# Matrix.net
KiCad netlist of a schematic drawn in Altium Designer
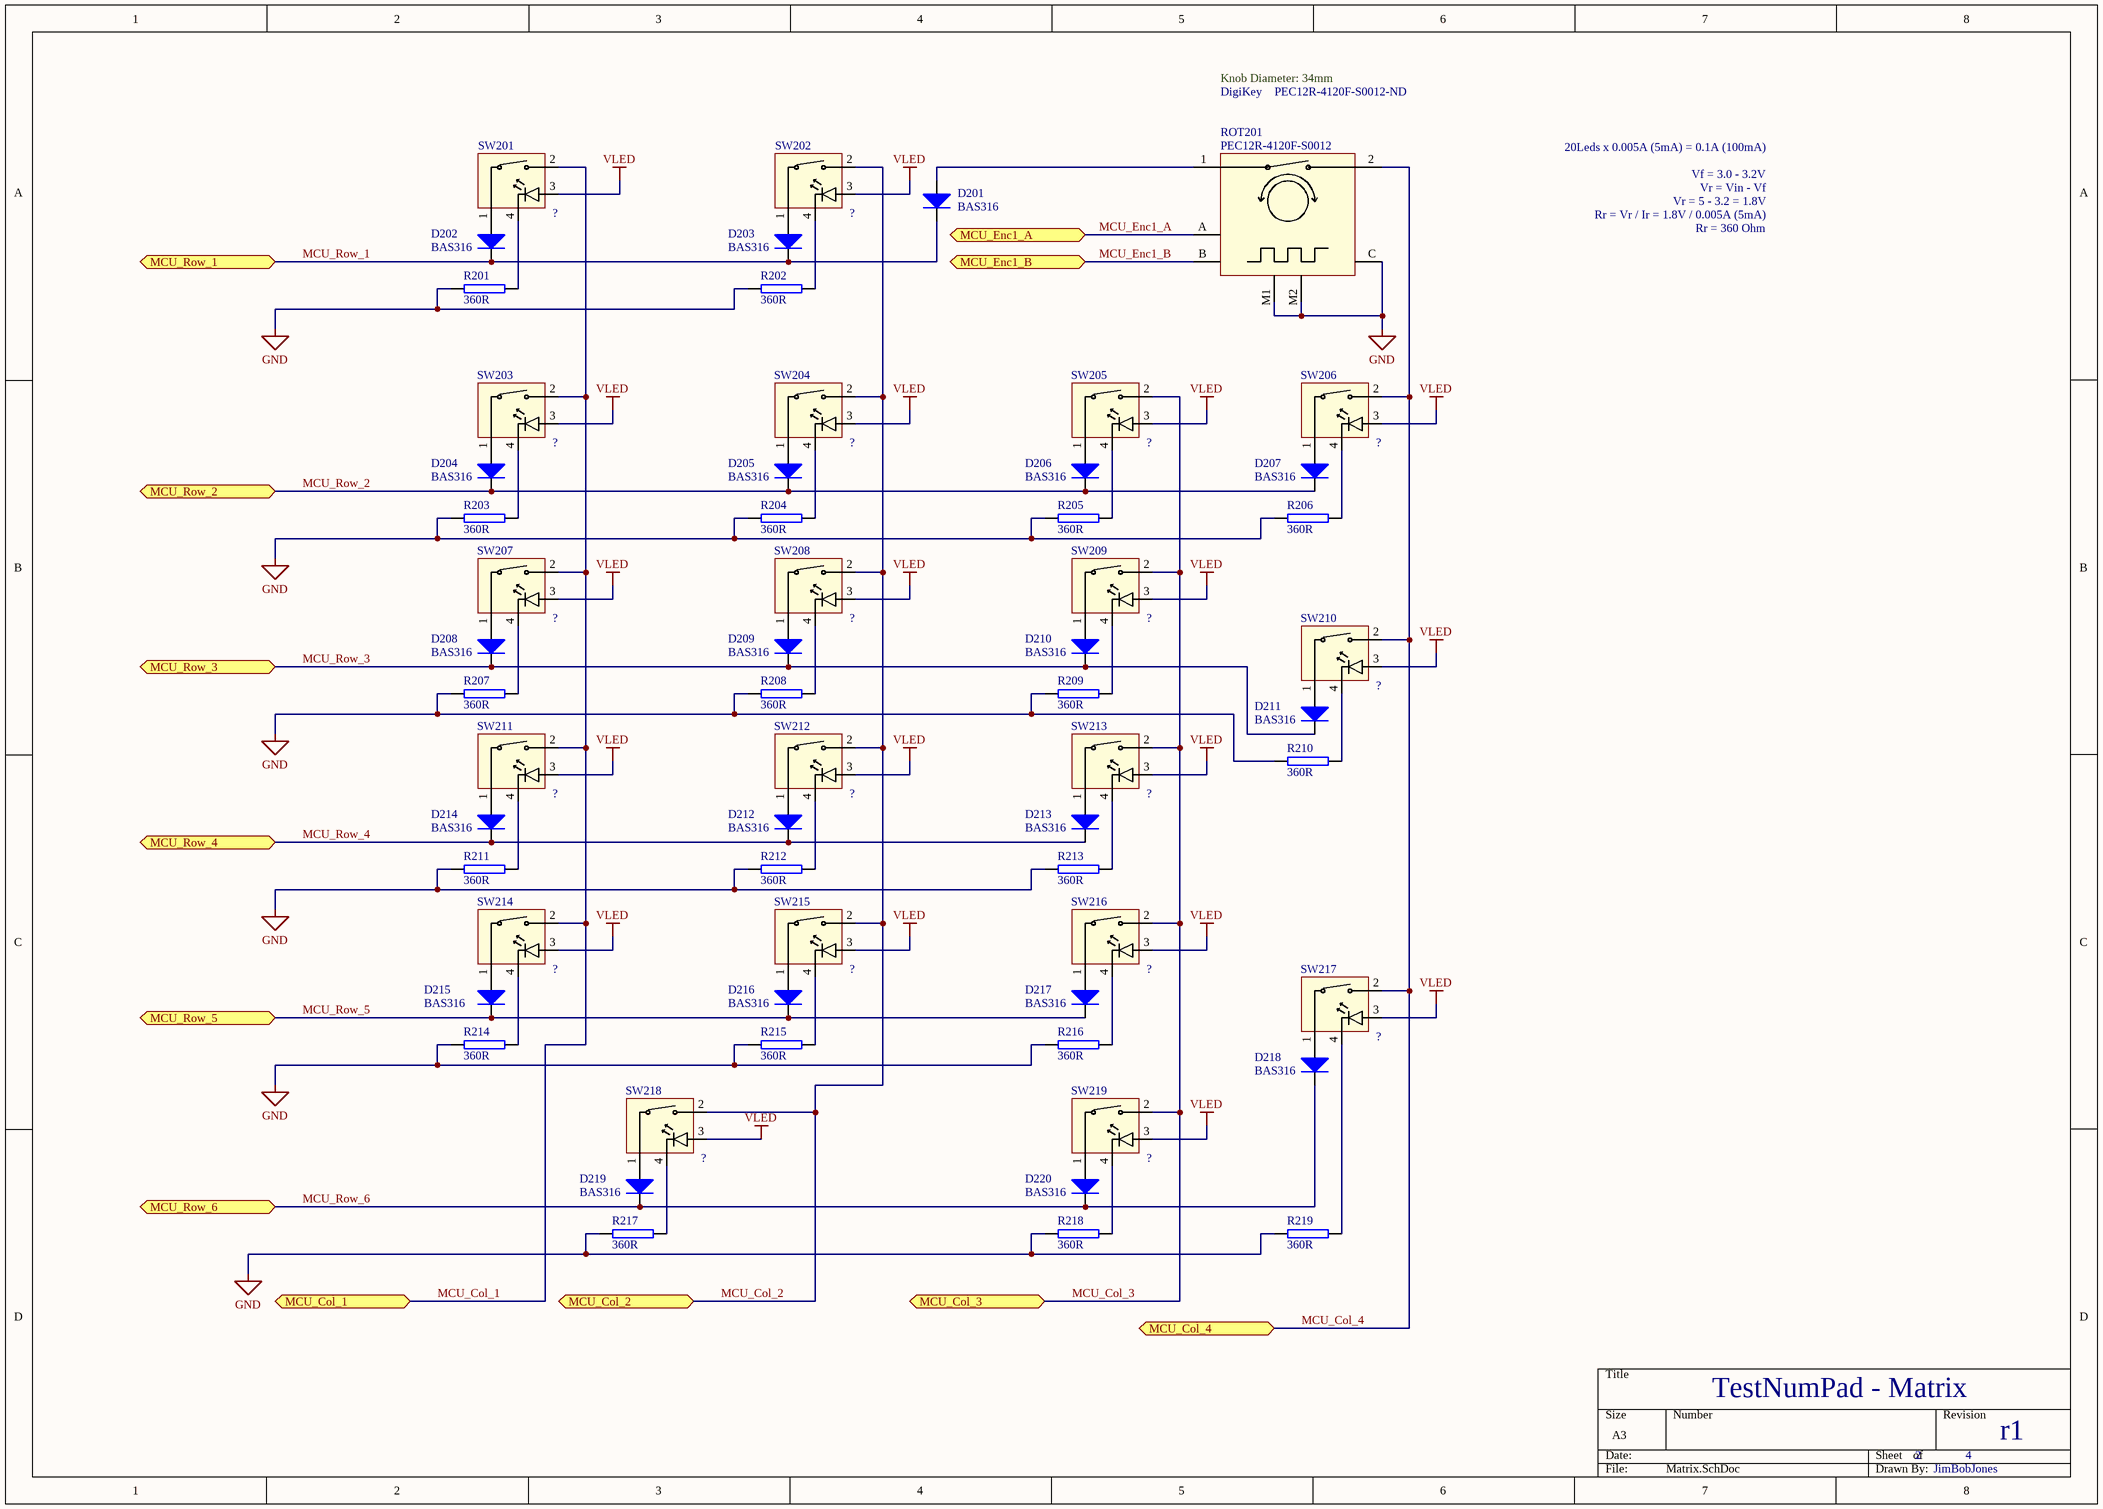
[diagram p0: Matrix.SchDoc]

(export (version "E")
  (design (tool "Eeschema 10.0.6"))
  (components
    (comp (ref "D201")
      (value "BAS316")
      (footprint "SOD110/SOD323")
      (description "Signal diode, 100V, 250mA, 400mW")
      (libsource (lib "JM_Keyboard") (part "Diode-BAS316"))
    )
    (comp (ref "D202")
      (value "BAS316")
      (footprint "SOD110/SOD323")
      (description "Signal diode, 100V, 250mA, 400mW")
      (libsource (lib "JM_Keyboard") (part "Diode-BAS316"))
    )
    (comp (ref "D203")
      (value "BAS316")
      (footprint "SOD110/SOD323")
      (description "Signal diode, 100V, 250mA, 400mW")
      (libsource (lib "JM_Keyboard") (part "Diode-BAS316"))
    )
    (comp (ref "D204")
      (value "BAS316")
      (footprint "SOD110/SOD323")
      (description "Signal diode, 100V, 250mA, 400mW")
      (libsource (lib "JM_Keyboard") (part "Diode-BAS316"))
    )
    (comp (ref "D205")
      (value "BAS316")
      (footprint "SOD110/SOD323")
      (description "Signal diode, 100V, 250mA, 400mW")
      (libsource (lib "JM_Keyboard") (part "Diode-BAS316"))
    )
    (comp (ref "D206")
      (value "BAS316")
      (footprint "SOD110/SOD323")
      (description "Signal diode, 100V, 250mA, 400mW")
      (libsource (lib "JM_Keyboard") (part "Diode-BAS316"))
    )
    (comp (ref "D207")
      (value "BAS316")
      (footprint "SOD110/SOD323")
      (description "Signal diode, 100V, 250mA, 400mW")
      (libsource (lib "JM_Keyboard") (part "Diode-BAS316"))
    )
    (comp (ref "D208")
      (value "BAS316")
      (footprint "SOD110/SOD323")
      (description "Signal diode, 100V, 250mA, 400mW")
      (libsource (lib "JM_Keyboard") (part "Diode-BAS316"))
    )
    (comp (ref "D209")
      (value "BAS316")
      (footprint "SOD110/SOD323")
      (description "Signal diode, 100V, 250mA, 400mW")
      (libsource (lib "JM_Keyboard") (part "Diode-BAS316"))
    )
    (comp (ref "D210")
      (value "BAS316")
      (footprint "SOD110/SOD323")
      (description "Signal diode, 100V, 250mA, 400mW")
      (libsource (lib "JM_Keyboard") (part "Diode-BAS316"))
    )
    (comp (ref "D211")
      (value "BAS316")
      (footprint "SOD110/SOD323")
      (description "Signal diode, 100V, 250mA, 400mW")
      (libsource (lib "JM_Keyboard") (part "Diode-BAS316"))
    )
    (comp (ref "D212")
      (value "BAS316")
      (footprint "SOD110/SOD323")
      (description "Signal diode, 100V, 250mA, 400mW")
      (libsource (lib "JM_Keyboard") (part "Diode-BAS316"))
    )
    (comp (ref "D213")
      (value "BAS316")
      (footprint "SOD110/SOD323")
      (description "Signal diode, 100V, 250mA, 400mW")
      (libsource (lib "JM_Keyboard") (part "Diode-BAS316"))
    )
    (comp (ref "D214")
      (value "BAS316")
      (footprint "SOD110/SOD323")
      (description "Signal diode, 100V, 250mA, 400mW")
      (libsource (lib "JM_Keyboard") (part "Diode-BAS316"))
    )
    (comp (ref "D215")
      (value "BAS316")
      (footprint "SOD110/SOD323")
      (description "Signal diode, 100V, 250mA, 400mW")
      (libsource (lib "JM_Keyboard") (part "Diode-BAS316"))
    )
    (comp (ref "D216")
      (value "BAS316")
      (footprint "SOD110/SOD323")
      (description "Signal diode, 100V, 250mA, 400mW")
      (libsource (lib "JM_Keyboard") (part "Diode-BAS316"))
    )
    (comp (ref "D217")
      (value "BAS316")
      (footprint "SOD110/SOD323")
      (description "Signal diode, 100V, 250mA, 400mW")
      (libsource (lib "JM_Keyboard") (part "Diode-BAS316"))
    )
    (comp (ref "D218")
      (value "BAS316")
      (footprint "SOD110/SOD323")
      (description "Signal diode, 100V, 250mA, 400mW")
      (libsource (lib "JM_Keyboard") (part "Diode-BAS316"))
    )
    (comp (ref "D219")
      (value "BAS316")
      (footprint "SOD110/SOD323")
      (description "Signal diode, 100V, 250mA, 400mW")
      (libsource (lib "JM_Keyboard") (part "Diode-BAS316"))
    )
    (comp (ref "D220")
      (value "BAS316")
      (footprint "SOD110/SOD323")
      (description "Signal diode, 100V, 250mA, 400mW")
      (libsource (lib "JM_Keyboard") (part "Diode-BAS316"))
    )
    (comp (ref "R201")
      (value "360R")
      (footprint "2012R-360")
      (description "RESISTOR 2012 1/4 WATT THIN FILM")
      (libsource (lib "JM_Keyboard") (part "2012R-360"))
    )
    (comp (ref "R202")
      (value "360R")
      (footprint "2012R-360")
      (description "RESISTOR 2012 1/4 WATT THIN FILM")
      (libsource (lib "JM_Keyboard") (part "2012R-360"))
    )
    (comp (ref "R203")
      (value "360R")
      (footprint "2012R-360")
      (description "RESISTOR 2012 1/4 WATT THIN FILM")
      (libsource (lib "JM_Keyboard") (part "2012R-360"))
    )
    (comp (ref "R204")
      (value "360R")
      (footprint "2012R-360")
      (description "RESISTOR 2012 1/4 WATT THIN FILM")
      (libsource (lib "JM_Keyboard") (part "2012R-360"))
    )
    (comp (ref "R205")
      (value "360R")
      (footprint "2012R-360")
      (description "RESISTOR 2012 1/4 WATT THIN FILM")
      (libsource (lib "JM_Keyboard") (part "2012R-360"))
    )
    (comp (ref "R206")
      (value "360R")
      (footprint "2012R-360")
      (description "RESISTOR 2012 1/4 WATT THIN FILM")
      (libsource (lib "JM_Keyboard") (part "2012R-360"))
    )
    (comp (ref "R207")
      (value "360R")
      (footprint "2012R-360")
      (description "RESISTOR 2012 1/4 WATT THIN FILM")
      (libsource (lib "JM_Keyboard") (part "2012R-360"))
    )
    (comp (ref "R208")
      (value "360R")
      (footprint "2012R-360")
      (description "RESISTOR 2012 1/4 WATT THIN FILM")
      (libsource (lib "JM_Keyboard") (part "2012R-360"))
    )
    (comp (ref "R209")
      (value "360R")
      (footprint "2012R-360")
      (description "RESISTOR 2012 1/4 WATT THIN FILM")
      (libsource (lib "JM_Keyboard") (part "2012R-360"))
    )
    (comp (ref "R210")
      (value "360R")
      (footprint "2012R-360")
      (description "RESISTOR 2012 1/4 WATT THIN FILM")
      (libsource (lib "JM_Keyboard") (part "2012R-360"))
    )
    (comp (ref "R211")
      (value "360R")
      (footprint "2012R-360")
      (description "RESISTOR 2012 1/4 WATT THIN FILM")
      (libsource (lib "JM_Keyboard") (part "2012R-360"))
    )
    (comp (ref "R212")
      (value "360R")
      (footprint "2012R-360")
      (description "RESISTOR 2012 1/4 WATT THIN FILM")
      (libsource (lib "JM_Keyboard") (part "2012R-360"))
    )
    (comp (ref "R213")
      (value "360R")
      (footprint "2012R-360")
      (description "RESISTOR 2012 1/4 WATT THIN FILM")
      (libsource (lib "JM_Keyboard") (part "2012R-360"))
    )
    (comp (ref "R214")
      (value "360R")
      (footprint "2012R-360")
      (description "RESISTOR 2012 1/4 WATT THIN FILM")
      (libsource (lib "JM_Keyboard") (part "2012R-360"))
    )
    (comp (ref "R215")
      (value "360R")
      (footprint "2012R-360")
      (description "RESISTOR 2012 1/4 WATT THIN FILM")
      (libsource (lib "JM_Keyboard") (part "2012R-360"))
    )
    (comp (ref "R216")
      (value "360R")
      (footprint "2012R-360")
      (description "RESISTOR 2012 1/4 WATT THIN FILM")
      (libsource (lib "JM_Keyboard") (part "2012R-360"))
    )
    (comp (ref "R217")
      (value "360R")
      (footprint "2012R-360")
      (description "RESISTOR 2012 1/4 WATT THIN FILM")
      (libsource (lib "JM_Keyboard") (part "2012R-360"))
    )
    (comp (ref "R218")
      (value "360R")
      (footprint "2012R-360")
      (description "RESISTOR 2012 1/4 WATT THIN FILM")
      (libsource (lib "JM_Keyboard") (part "2012R-360"))
    )
    (comp (ref "R219")
      (value "360R")
      (footprint "2012R-360")
      (description "RESISTOR 2012 1/4 WATT THIN FILM")
      (libsource (lib "JM_Keyboard") (part "2012R-360"))
    )
    (comp (ref "ROT201")
      (value "PEC12R-4120F-S0012")
      (footprint "PEC12R-4xxxF-Sxxxx-NoMod")
      (description "Burns 6mm D-shaft 2-Ch Rotary Encoder with switch, 12ppr, Vertical")
      (fields (field (name "SUPPLIER PART NUMBER 1") "PEC12R-4120F-S0012-ND"))
      (libsource (lib "JM_Keyboard") (part "PEC12R-Vert-Sw"))
    )
    (comp (ref "SW201")
      (value "MX_Apls")
      (footprint "MX-1U")
      (description "1U - MX_Alps Hybrid Footprint")
      (fields (field (name "KEY") "?"))
      (libsource (lib "JM_Keyboard") (part "MX-LED-1U"))
    )
    (comp (ref "SW202")
      (value "MX_Apls")
      (footprint "MX-1U")
      (description "1U - MX_Alps Hybrid Footprint")
      (fields (field (name "KEY") "?"))
      (libsource (lib "JM_Keyboard") (part "MX-LED-1U"))
    )
    (comp (ref "SW203")
      (value "MX_Apls")
      (footprint "MX-1U")
      (description "1U - MX_Alps Hybrid Footprint")
      (fields (field (name "KEY") "?"))
      (libsource (lib "JM_Keyboard") (part "MX-LED-1U"))
    )
    (comp (ref "SW204")
      (value "MX_Apls")
      (footprint "MX-1U")
      (description "1U - MX_Alps Hybrid Footprint")
      (fields (field (name "KEY") "?"))
      (libsource (lib "JM_Keyboard") (part "MX-LED-1U"))
    )
    (comp (ref "SW205")
      (value "MX_Apls")
      (footprint "MX-1U")
      (description "1U - MX_Alps Hybrid Footprint")
      (fields (field (name "KEY") "?"))
      (libsource (lib "JM_Keyboard") (part "MX-LED-1U"))
    )
    (comp (ref "SW206")
      (value "MX_Apls")
      (footprint "MX-1U")
      (description "1U - MX_Alps Hybrid Footprint")
      (fields (field (name "KEY") "?"))
      (libsource (lib "JM_Keyboard") (part "MX-LED-1U"))
    )
    (comp (ref "SW207")
      (value "MX_Apls")
      (footprint "MX-1U")
      (description "1U - MX_Alps Hybrid Footprint")
      (fields (field (name "KEY") "?"))
      (libsource (lib "JM_Keyboard") (part "MX-LED-1U"))
    )
    (comp (ref "SW208")
      (value "MX_Apls")
      (footprint "MX-1U")
      (description "1U - MX_Alps Hybrid Footprint")
      (fields (field (name "KEY") "?"))
      (libsource (lib "JM_Keyboard") (part "MX-LED-1U"))
    )
    (comp (ref "SW209")
      (value "MX_Apls")
      (footprint "MX-1U")
      (description "1U - MX_Alps Hybrid Footprint")
      (fields (field (name "KEY") "?"))
      (libsource (lib "JM_Keyboard") (part "MX-LED-1U"))
    )
    (comp (ref "SW210")
      (value "MX_Apls")
      (footprint "MX-2U")
      (description "1U - MX_Alps Hybrid Footprint")
      (fields (field (name "KEY") "?"))
      (libsource (lib "JM_Keyboard") (part "MX-LED-1U"))
    )
    (comp (ref "SW211")
      (value "MX_Apls")
      (footprint "MX-1U")
      (description "1U - MX_Alps Hybrid Footprint")
      (fields (field (name "KEY") "?"))
      (libsource (lib "JM_Keyboard") (part "MX-LED-1U"))
    )
    (comp (ref "SW212")
      (value "MX_Apls")
      (footprint "MX-1U")
      (description "1U - MX_Alps Hybrid Footprint")
      (fields (field (name "KEY") "?"))
      (libsource (lib "JM_Keyboard") (part "MX-LED-1U"))
    )
    (comp (ref "SW213")
      (value "MX_Apls")
      (footprint "MX-1U")
      (description "1U - MX_Alps Hybrid Footprint")
      (fields (field (name "KEY") "?"))
      (libsource (lib "JM_Keyboard") (part "MX-LED-1U"))
    )
    (comp (ref "SW214")
      (value "MX_Apls")
      (footprint "MX-1U")
      (description "1U - MX_Alps Hybrid Footprint")
      (fields (field (name "KEY") "?"))
      (libsource (lib "JM_Keyboard") (part "MX-LED-1U"))
    )
    (comp (ref "SW215")
      (value "MX_Apls")
      (footprint "MX-1U")
      (description "1U - MX_Alps Hybrid Footprint")
      (fields (field (name "KEY") "?"))
      (libsource (lib "JM_Keyboard") (part "MX-LED-1U"))
    )
    (comp (ref "SW216")
      (value "MX_Apls")
      (footprint "MX-1U")
      (description "1U - MX_Alps Hybrid Footprint")
      (fields (field (name "KEY") "?"))
      (libsource (lib "JM_Keyboard") (part "MX-LED-1U"))
    )
    (comp (ref "SW217")
      (value "MX_Apls")
      (footprint "MX-2U")
      (description "1U - MX_Alps Hybrid Footprint")
      (fields (field (name "KEY") "?"))
      (libsource (lib "JM_Keyboard") (part "MX-LED-1U"))
    )
    (comp (ref "SW218")
      (value "MX_Apls")
      (footprint "MX-2U")
      (description "1U - MX_Alps Hybrid Footprint")
      (fields (field (name "KEY") "?"))
      (libsource (lib "JM_Keyboard") (part "MX-LED-1U"))
    )
    (comp (ref "SW219")
      (value "MX_Apls")
      (footprint "MX-1U")
      (description "1U - MX_Alps Hybrid Footprint")
      (fields (field (name "KEY") "?"))
      (libsource (lib "JM_Keyboard") (part "MX-LED-1U"))
    )
  )
  (nets
    (net (code "1") (name "/MCU_Col_1") (class "Default")
      (node (ref "SW201") (pin "2") (pinfunction "2_2") (pintype "passive"))
      (node (ref "SW203") (pin "2") (pinfunction "2_2") (pintype "passive"))
      (node (ref "SW207") (pin "2") (pinfunction "2_2") (pintype "passive"))
      (node (ref "SW211") (pin "2") (pinfunction "2_2") (pintype "passive"))
      (node (ref "SW214") (pin "2") (pinfunction "2_2") (pintype "passive"))
    )
    (net (code "2") (name "/MCU_Col_2") (class "Default")
      (node (ref "SW202") (pin "2") (pinfunction "2_2") (pintype "passive"))
      (node (ref "SW204") (pin "2") (pinfunction "2_2") (pintype "passive"))
      (node (ref "SW208") (pin "2") (pinfunction "2_2") (pintype "passive"))
      (node (ref "SW212") (pin "2") (pinfunction "2_2") (pintype "passive"))
      (node (ref "SW215") (pin "2") (pinfunction "2_2") (pintype "passive"))
      (node (ref "SW218") (pin "2") (pinfunction "2_2") (pintype "passive"))
    )
    (net (code "3") (name "/MCU_Col_3") (class "Default")
      (node (ref "SW205") (pin "2") (pinfunction "2_2") (pintype "passive"))
      (node (ref "SW209") (pin "2") (pinfunction "2_2") (pintype "passive"))
      (node (ref "SW213") (pin "2") (pinfunction "2_2") (pintype "passive"))
      (node (ref "SW216") (pin "2") (pinfunction "2_2") (pintype "passive"))
      (node (ref "SW219") (pin "2") (pinfunction "2_2") (pintype "passive"))
    )
    (net (code "4") (name "/MCU_Col_4") (class "Default")
      (node (ref "ROT201") (pin "2") (pinfunction "2_2") (pintype "passive"))
      (node (ref "SW206") (pin "2") (pinfunction "2_2") (pintype "passive"))
      (node (ref "SW210") (pin "2") (pinfunction "2_2") (pintype "passive"))
      (node (ref "SW217") (pin "2") (pinfunction "2_2") (pintype "passive"))
    )
    (net (code "5") (name "/MCU_Enc1_A") (class "Default")
      (node (ref "ROT201") (pin "A") (pinfunction "A_A") (pintype "passive"))
    )
    (net (code "6") (name "/MCU_Enc1_B") (class "Default")
      (node (ref "ROT201") (pin "B") (pinfunction "B_B") (pintype "passive"))
    )
    (net (code "7") (name "/MCU_Row_1") (class "Default")
      (node (ref "D201") (pin "K") (pinfunction "-_K") (pintype "passive"))
      (node (ref "D202") (pin "K") (pinfunction "-_K") (pintype "passive"))
      (node (ref "D203") (pin "K") (pinfunction "-_K") (pintype "passive"))
    )
    (net (code "8") (name "/MCU_Row_2") (class "Default")
      (node (ref "D204") (pin "K") (pinfunction "-_K") (pintype "passive"))
      (node (ref "D205") (pin "K") (pinfunction "-_K") (pintype "passive"))
      (node (ref "D206") (pin "K") (pinfunction "-_K") (pintype "passive"))
      (node (ref "D207") (pin "K") (pinfunction "-_K") (pintype "passive"))
    )
    (net (code "9") (name "/MCU_Row_3") (class "Default")
      (node (ref "D208") (pin "K") (pinfunction "-_K") (pintype "passive"))
      (node (ref "D209") (pin "K") (pinfunction "-_K") (pintype "passive"))
      (node (ref "D210") (pin "K") (pinfunction "-_K") (pintype "passive"))
      (node (ref "D211") (pin "K") (pinfunction "-_K") (pintype "passive"))
    )
    (net (code "10") (name "/MCU_Row_4") (class "Default")
      (node (ref "D212") (pin "K") (pinfunction "-_K") (pintype "passive"))
      (node (ref "D213") (pin "K") (pinfunction "-_K") (pintype "passive"))
      (node (ref "D214") (pin "K") (pinfunction "-_K") (pintype "passive"))
    )
    (net (code "11") (name "/MCU_Row_5") (class "Default")
      (node (ref "D215") (pin "K") (pinfunction "-_K") (pintype "passive"))
      (node (ref "D216") (pin "K") (pinfunction "-_K") (pintype "passive"))
      (node (ref "D217") (pin "K") (pinfunction "-_K") (pintype "passive"))
    )
    (net (code "12") (name "/MCU_Row_6") (class "Default")
      (node (ref "D218") (pin "K") (pinfunction "-_K") (pintype "passive"))
      (node (ref "D219") (pin "K") (pinfunction "-_K") (pintype "passive"))
      (node (ref "D220") (pin "K") (pinfunction "-_K") (pintype "passive"))
    )
    (net (code "13") (name "GND") (class "Default")
      (node (ref "R201") (pin "2") (pintype "passive"))
      (node (ref "R202") (pin "2") (pintype "passive"))
      (node (ref "R203") (pin "1") (pintype "passive"))
      (node (ref "R204") (pin "1") (pintype "passive"))
      (node (ref "R205") (pin "1") (pintype "passive"))
      (node (ref "R206") (pin "1") (pintype "passive"))
      (node (ref "R207") (pin "1") (pintype "passive"))
      (node (ref "R208") (pin "1") (pintype "passive"))
      (node (ref "R209") (pin "1") (pintype "passive"))
      (node (ref "R210") (pin "1") (pintype "passive"))
      (node (ref "R211") (pin "1") (pintype "passive"))
      (node (ref "R212") (pin "1") (pintype "passive"))
      (node (ref "R213") (pin "1") (pintype "passive"))
      (node (ref "R214") (pin "1") (pintype "passive"))
      (node (ref "R215") (pin "1") (pintype "passive"))
      (node (ref "R216") (pin "1") (pintype "passive"))
      (node (ref "R217") (pin "1") (pintype "passive"))
      (node (ref "R218") (pin "1") (pintype "passive"))
      (node (ref "R219") (pin "1") (pintype "passive"))
      (node (ref "ROT201") (pin "C") (pinfunction "C_C") (pintype "passive"))
      (node (ref "ROT201") (pin "M1") (pinfunction "M_M1") (pintype "passive"))
      (node (ref "ROT201") (pin "M2") (pinfunction "M2_M2") (pintype "passive"))
    )
    (net (code "14") (name "Net-(D201-+)") (class "Default")
      (node (ref "D201") (pin "A") (pinfunction "+_A") (pintype "passive"))
      (node (ref "ROT201") (pin "1") (pinfunction "1_1") (pintype "passive"))
    )
    (net (code "15") (name "Net-(D202-+)") (class "Default")
      (node (ref "D202") (pin "A") (pinfunction "+_A") (pintype "passive"))
      (node (ref "SW201") (pin "1") (pinfunction "1_1") (pintype "passive"))
    )
    (net (code "16") (name "Net-(D203-+)") (class "Default")
      (node (ref "D203") (pin "A") (pinfunction "+_A") (pintype "passive"))
      (node (ref "SW202") (pin "1") (pinfunction "1_1") (pintype "passive"))
    )
    (net (code "17") (name "Net-(D204-+)") (class "Default")
      (node (ref "D204") (pin "A") (pinfunction "+_A") (pintype "passive"))
      (node (ref "SW203") (pin "1") (pinfunction "1_1") (pintype "passive"))
    )
    (net (code "18") (name "Net-(D205-+)") (class "Default")
      (node (ref "D205") (pin "A") (pinfunction "+_A") (pintype "passive"))
      (node (ref "SW204") (pin "1") (pinfunction "1_1") (pintype "passive"))
    )
    (net (code "19") (name "Net-(D206-+)") (class "Default")
      (node (ref "D206") (pin "A") (pinfunction "+_A") (pintype "passive"))
      (node (ref "SW205") (pin "1") (pinfunction "1_1") (pintype "passive"))
    )
    (net (code "20") (name "Net-(D207-+)") (class "Default")
      (node (ref "D207") (pin "A") (pinfunction "+_A") (pintype "passive"))
      (node (ref "SW206") (pin "1") (pinfunction "1_1") (pintype "passive"))
    )
    (net (code "21") (name "Net-(D208-+)") (class "Default")
      (node (ref "D208") (pin "A") (pinfunction "+_A") (pintype "passive"))
      (node (ref "SW207") (pin "1") (pinfunction "1_1") (pintype "passive"))
    )
    (net (code "22") (name "Net-(D209-+)") (class "Default")
      (node (ref "D209") (pin "A") (pinfunction "+_A") (pintype "passive"))
      (node (ref "SW208") (pin "1") (pinfunction "1_1") (pintype "passive"))
    )
    (net (code "23") (name "Net-(D210-+)") (class "Default")
      (node (ref "D210") (pin "A") (pinfunction "+_A") (pintype "passive"))
      (node (ref "SW209") (pin "1") (pinfunction "1_1") (pintype "passive"))
    )
    (net (code "24") (name "Net-(D211-+)") (class "Default")
      (node (ref "D211") (pin "A") (pinfunction "+_A") (pintype "passive"))
      (node (ref "SW210") (pin "1") (pinfunction "1_1") (pintype "passive"))
    )
    (net (code "25") (name "Net-(D212-+)") (class "Default")
      (node (ref "D212") (pin "A") (pinfunction "+_A") (pintype "passive"))
      (node (ref "SW212") (pin "1") (pinfunction "1_1") (pintype "passive"))
    )
    (net (code "26") (name "Net-(D213-+)") (class "Default")
      (node (ref "D213") (pin "A") (pinfunction "+_A") (pintype "passive"))
      (node (ref "SW213") (pin "1") (pinfunction "1_1") (pintype "passive"))
    )
    (net (code "27") (name "Net-(D214-+)") (class "Default")
      (node (ref "D214") (pin "A") (pinfunction "+_A") (pintype "passive"))
      (node (ref "SW211") (pin "1") (pinfunction "1_1") (pintype "passive"))
    )
    (net (code "28") (name "Net-(D215-+)") (class "Default")
      (node (ref "D215") (pin "A") (pinfunction "+_A") (pintype "passive"))
      (node (ref "SW214") (pin "1") (pinfunction "1_1") (pintype "passive"))
    )
    (net (code "29") (name "Net-(D216-+)") (class "Default")
      (node (ref "D216") (pin "A") (pinfunction "+_A") (pintype "passive"))
      (node (ref "SW215") (pin "1") (pinfunction "1_1") (pintype "passive"))
    )
    (net (code "30") (name "Net-(D217-+)") (class "Default")
      (node (ref "D217") (pin "A") (pinfunction "+_A") (pintype "passive"))
      (node (ref "SW216") (pin "1") (pinfunction "1_1") (pintype "passive"))
    )
    (net (code "31") (name "Net-(D218-+)") (class "Default")
      (node (ref "D218") (pin "A") (pinfunction "+_A") (pintype "passive"))
      (node (ref "SW217") (pin "1") (pinfunction "1_1") (pintype "passive"))
    )
    (net (code "32") (name "Net-(D219-+)") (class "Default")
      (node (ref "D219") (pin "A") (pinfunction "+_A") (pintype "passive"))
      (node (ref "SW218") (pin "1") (pinfunction "1_1") (pintype "passive"))
    )
    (net (code "33") (name "Net-(D220-+)") (class "Default")
      (node (ref "D220") (pin "A") (pinfunction "+_A") (pintype "passive"))
      (node (ref "SW219") (pin "1") (pinfunction "1_1") (pintype "passive"))
    )
    (net (code "34") (name "Net-(R201-Pad1)") (class "Default")
      (node (ref "R201") (pin "1") (pintype "passive"))
      (node (ref "SW201") (pin "4") (pinfunction "4_4") (pintype "passive"))
    )
    (net (code "35") (name "Net-(R202-Pad1)") (class "Default")
      (node (ref "R202") (pin "1") (pintype "passive"))
      (node (ref "SW202") (pin "4") (pinfunction "4_4") (pintype "passive"))
    )
    (net (code "36") (name "Net-(R203-Pad2)") (class "Default")
      (node (ref "R203") (pin "2") (pintype "passive"))
      (node (ref "SW203") (pin "4") (pinfunction "4_4") (pintype "passive"))
    )
    (net (code "37") (name "Net-(R204-Pad2)") (class "Default")
      (node (ref "R204") (pin "2") (pintype "passive"))
      (node (ref "SW204") (pin "4") (pinfunction "4_4") (pintype "passive"))
    )
    (net (code "38") (name "Net-(R205-Pad2)") (class "Default")
      (node (ref "R205") (pin "2") (pintype "passive"))
      (node (ref "SW205") (pin "4") (pinfunction "4_4") (pintype "passive"))
    )
    (net (code "39") (name "Net-(R206-Pad2)") (class "Default")
      (node (ref "R206") (pin "2") (pintype "passive"))
      (node (ref "SW206") (pin "4") (pinfunction "4_4") (pintype "passive"))
    )
    (net (code "40") (name "Net-(R207-Pad2)") (class "Default")
      (node (ref "R207") (pin "2") (pintype "passive"))
      (node (ref "SW207") (pin "4") (pinfunction "4_4") (pintype "passive"))
    )
    (net (code "41") (name "Net-(R208-Pad2)") (class "Default")
      (node (ref "R208") (pin "2") (pintype "passive"))
      (node (ref "SW208") (pin "4") (pinfunction "4_4") (pintype "passive"))
    )
    (net (code "42") (name "Net-(R209-Pad2)") (class "Default")
      (node (ref "R209") (pin "2") (pintype "passive"))
      (node (ref "SW209") (pin "4") (pinfunction "4_4") (pintype "passive"))
    )
    (net (code "43") (name "Net-(R210-Pad2)") (class "Default")
      (node (ref "R210") (pin "2") (pintype "passive"))
      (node (ref "SW210") (pin "4") (pinfunction "4_4") (pintype "passive"))
    )
    (net (code "44") (name "Net-(R211-Pad2)") (class "Default")
      (node (ref "R211") (pin "2") (pintype "passive"))
      (node (ref "SW211") (pin "4") (pinfunction "4_4") (pintype "passive"))
    )
    (net (code "45") (name "Net-(R212-Pad2)") (class "Default")
      (node (ref "R212") (pin "2") (pintype "passive"))
      (node (ref "SW212") (pin "4") (pinfunction "4_4") (pintype "passive"))
    )
    (net (code "46") (name "Net-(R213-Pad2)") (class "Default")
      (node (ref "R213") (pin "2") (pintype "passive"))
      (node (ref "SW213") (pin "4") (pinfunction "4_4") (pintype "passive"))
    )
    (net (code "47") (name "Net-(R214-Pad2)") (class "Default")
      (node (ref "R214") (pin "2") (pintype "passive"))
      (node (ref "SW214") (pin "4") (pinfunction "4_4") (pintype "passive"))
    )
    (net (code "48") (name "Net-(R215-Pad2)") (class "Default")
      (node (ref "R215") (pin "2") (pintype "passive"))
      (node (ref "SW215") (pin "4") (pinfunction "4_4") (pintype "passive"))
    )
    (net (code "49") (name "Net-(R216-Pad2)") (class "Default")
      (node (ref "R216") (pin "2") (pintype "passive"))
      (node (ref "SW216") (pin "4") (pinfunction "4_4") (pintype "passive"))
    )
    (net (code "50") (name "Net-(R217-Pad2)") (class "Default")
      (node (ref "R217") (pin "2") (pintype "passive"))
      (node (ref "SW218") (pin "4") (pinfunction "4_4") (pintype "passive"))
    )
    (net (code "51") (name "Net-(R218-Pad2)") (class "Default")
      (node (ref "R218") (pin "2") (pintype "passive"))
      (node (ref "SW219") (pin "4") (pinfunction "4_4") (pintype "passive"))
    )
    (net (code "52") (name "Net-(R219-Pad2)") (class "Default")
      (node (ref "R219") (pin "2") (pintype "passive"))
      (node (ref "SW217") (pin "4") (pinfunction "4_4") (pintype "passive"))
    )
    (net (code "53") (name "VLED") (class "Default")
      (node (ref "SW201") (pin "3") (pinfunction "3_3") (pintype "passive"))
      (node (ref "SW202") (pin "3") (pinfunction "3_3") (pintype "passive"))
      (node (ref "SW203") (pin "3") (pinfunction "3_3") (pintype "passive"))
      (node (ref "SW204") (pin "3") (pinfunction "3_3") (pintype "passive"))
      (node (ref "SW205") (pin "3") (pinfunction "3_3") (pintype "passive"))
      (node (ref "SW206") (pin "3") (pinfunction "3_3") (pintype "passive"))
      (node (ref "SW207") (pin "3") (pinfunction "3_3") (pintype "passive"))
      (node (ref "SW208") (pin "3") (pinfunction "3_3") (pintype "passive"))
      (node (ref "SW209") (pin "3") (pinfunction "3_3") (pintype "passive"))
      (node (ref "SW210") (pin "3") (pinfunction "3_3") (pintype "passive"))
      (node (ref "SW211") (pin "3") (pinfunction "3_3") (pintype "passive"))
      (node (ref "SW212") (pin "3") (pinfunction "3_3") (pintype "passive"))
      (node (ref "SW213") (pin "3") (pinfunction "3_3") (pintype "passive"))
      (node (ref "SW214") (pin "3") (pinfunction "3_3") (pintype "passive"))
      (node (ref "SW215") (pin "3") (pinfunction "3_3") (pintype "passive"))
      (node (ref "SW216") (pin "3") (pinfunction "3_3") (pintype "passive"))
      (node (ref "SW217") (pin "3") (pinfunction "3_3") (pintype "passive"))
      (node (ref "SW218") (pin "3") (pinfunction "3_3") (pintype "passive"))
      (node (ref "SW219") (pin "3") (pinfunction "3_3") (pintype "passive"))
    )
  )
)
